# Main_board_rev2.net
KiCad netlist of a schematic drawn in EAGLE
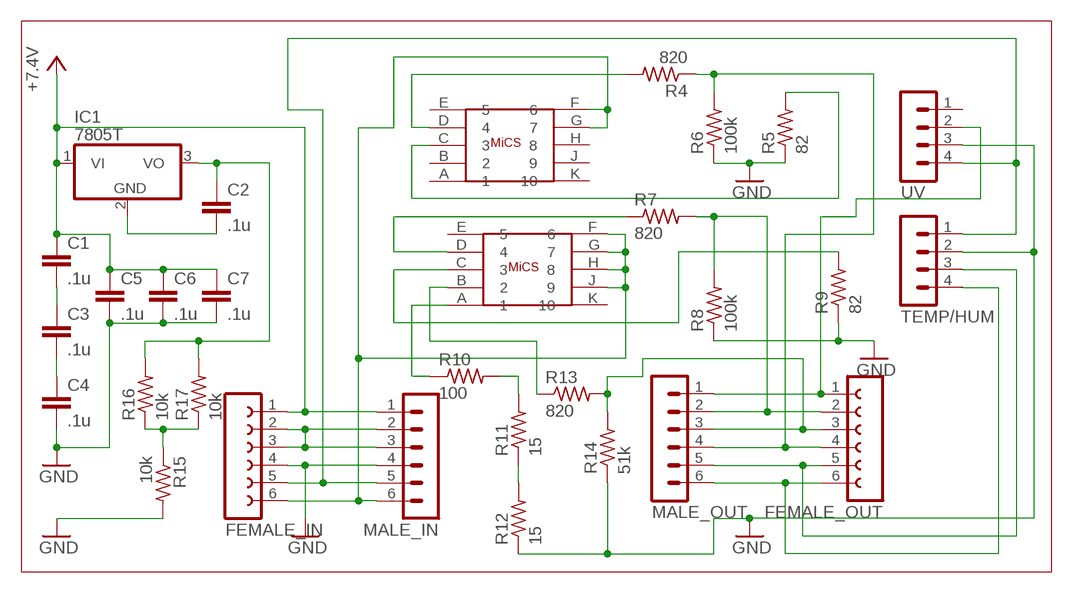
[diagram p0: schematic, sheet 1]

(export (version "E")
  (design (tool "Eeschema 10.0.6"))
  (components
    (comp (ref "2614")
      (value "MICS_SMD")
      (footprint "eagle-import:MICS_SOCKET")
      (libsource (lib "eagle-import") (part "MICS_SMD"))
    )
    (comp (ref "4514")
      (value "MICS_SMD")
      (footprint "eagle-import:MICS_SOCKET")
      (libsource (lib "eagle-import") (part "MICS_SMD"))
    )
    (comp (ref "C1")
      (value ".1u")
      (footprint "eagle-import:C2.5-3")
      (libsource (lib "eagle-import") (part "C2,5-3"))
    )
    (comp (ref "C2")
      (value ".1u")
      (footprint "eagle-import:C2.5-3")
      (libsource (lib "eagle-import") (part "C2,5-3"))
    )
    (comp (ref "C3")
      (value ".1u")
      (footprint "eagle-import:C2.5-3")
      (libsource (lib "eagle-import") (part "C2,5-3"))
    )
    (comp (ref "C4")
      (value ".1u")
      (footprint "eagle-import:C2.5-3")
      (libsource (lib "eagle-import") (part "C2,5-3"))
    )
    (comp (ref "C5")
      (value ".1u")
      (footprint "eagle-import:C2.5-3")
      (libsource (lib "eagle-import") (part "C2,5-3"))
    )
    (comp (ref "C6")
      (value ".1u")
      (footprint "eagle-import:C2.5-3")
      (libsource (lib "eagle-import") (part "C2,5-3"))
    )
    (comp (ref "C7")
      (value ".1u")
      (footprint "eagle-import:C2.5-3")
      (libsource (lib "eagle-import") (part "C2,5-3"))
    )
    (comp (ref "FEMALE_IN")
      (value "FE06W")
      (footprint "eagle-import:FE06W")
      (libsource (lib "eagle-import") (part "FE06W"))
    )
    (comp (ref "FEMALE_OUT")
      (value "FE06W")
      (footprint "eagle-import:FE06W")
      (libsource (lib "eagle-import") (part "FE06W"))
    )
    (comp (ref "IC1")
      (value "7805T")
      (footprint "eagle-import:TO220H")
      (libsource (lib "eagle-import") (part "78T05"))
    )
    (comp (ref "MALE_IN")
      (value "MA06-1")
      (footprint "eagle-import:MA06-1")
      (libsource (lib "eagle-import") (part "MA06-1"))
    )
    (comp (ref "MALE_OUT")
      (value "MA06-1")
      (footprint "eagle-import:MA06-1")
      (libsource (lib "eagle-import") (part "MA06-1"))
    )
    (comp (ref "R4")
      (value "820")
      (footprint "eagle-import:0204_7")
      (libsource (lib "eagle-import") (part "R-US_0204/7"))
    )
    (comp (ref "R5")
      (value "82")
      (footprint "eagle-import:0204_7")
      (libsource (lib "eagle-import") (part "R-US_0204/7"))
    )
    (comp (ref "R6")
      (value "100k")
      (footprint "eagle-import:0204_7")
      (libsource (lib "eagle-import") (part "R-US_0204/7"))
    )
    (comp (ref "R7")
      (value "820")
      (footprint "eagle-import:0204_7")
      (libsource (lib "eagle-import") (part "R-US_0204/7"))
    )
    (comp (ref "R8")
      (value "100k")
      (footprint "eagle-import:0204_7")
      (libsource (lib "eagle-import") (part "R-US_0204/7"))
    )
    (comp (ref "R9")
      (value "82")
      (footprint "eagle-import:0204_7")
      (libsource (lib "eagle-import") (part "R-US_0204/7"))
    )
    (comp (ref "R10")
      (value "100")
      (footprint "eagle-import:0204_7")
      (libsource (lib "eagle-import") (part "R-US_0204/7"))
    )
    (comp (ref "R11")
      (value "15")
      (footprint "eagle-import:0204_7")
      (libsource (lib "eagle-import") (part "R-US_0204/7"))
    )
    (comp (ref "R12")
      (value "15")
      (footprint "eagle-import:0204_7")
      (libsource (lib "eagle-import") (part "R-US_0204/7"))
    )
    (comp (ref "R13")
      (value "820")
      (footprint "eagle-import:0204_7")
      (libsource (lib "eagle-import") (part "R-US_0204/7"))
    )
    (comp (ref "R14")
      (value "51k")
      (footprint "eagle-import:0204_7")
      (libsource (lib "eagle-import") (part "R-US_0204/7"))
    )
    (comp (ref "R15")
      (value "10k")
      (footprint "eagle-import:0204_7")
      (libsource (lib "eagle-import") (part "resistor_R-US_0204/7"))
    )
    (comp (ref "R16")
      (value "10k")
      (footprint "eagle-import:0204_7")
      (libsource (lib "eagle-import") (part "resistor_R-US_0204/7"))
    )
    (comp (ref "R17")
      (value "10k")
      (footprint "eagle-import:0204_7")
      (libsource (lib "eagle-import") (part "resistor_R-US_0204/7"))
    )
    (comp (ref "TEMP/HUM")
      (value "MA04-1")
      (footprint "eagle-import:MA04-1")
      (libsource (lib "eagle-import") (part "MA04-1"))
    )
    (comp (ref "UV")
      (value "MA04-1")
      (footprint "eagle-import:MA04-1")
      (libsource (lib "eagle-import") (part "MA04-1"))
    )
  )
  (nets
    (net (code "1") (name "+7.4V") (class "Default")
      (node (ref "C1") (pin "1") (pinfunction "1_1") (pintype "passive"))
      (node (ref "C5") (pin "1") (pinfunction "1_1") (pintype "passive"))
      (node (ref "C6") (pin "1") (pinfunction "1_1") (pintype "passive"))
      (node (ref "C7") (pin "1") (pinfunction "1_1") (pintype "passive"))
      (node (ref "FEMALE_IN") (pin "1") (pinfunction "1_1") (pintype "passive"))
      (node (ref "IC1") (pin "1") (pinfunction "VI_1") (pintype "input"))
      (node (ref "MALE_IN") (pin "1") (pinfunction "1_1") (pintype "passive"))
    )
    (net (code "2") (name "GND") (class "Default")
      (node (ref "C4") (pin "2") (pinfunction "2_2") (pintype "passive"))
      (node (ref "C5") (pin "2") (pinfunction "2_2") (pintype "passive"))
      (node (ref "C6") (pin "2") (pinfunction "2_2") (pintype "passive"))
      (node (ref "C7") (pin "2") (pinfunction "2_2") (pintype "passive"))
      (node (ref "FEMALE_IN") (pin "4") (pinfunction "4_4") (pintype "passive"))
      (node (ref "MALE_IN") (pin "4") (pinfunction "4_4") (pintype "passive"))
      (node (ref "R12") (pin "1") (pinfunction "1_1") (pintype "passive"))
      (node (ref "R14") (pin "1") (pinfunction "1_1") (pintype "passive"))
      (node (ref "R15") (pin "2") (pinfunction "2_2") (pintype "passive"))
      (node (ref "R5") (pin "1") (pinfunction "1_1") (pintype "passive"))
      (node (ref "R6") (pin "1") (pinfunction "1_1") (pintype "passive"))
      (node (ref "R8") (pin "1") (pinfunction "1_1") (pintype "passive"))
      (node (ref "R9") (pin "1") (pinfunction "1_1") (pintype "passive"))
      (node (ref "TEMP/HUM") (pin "2") (pinfunction "2_2") (pintype "passive"))
      (node (ref "UV") (pin "3") (pinfunction "3_3") (pintype "passive"))
    )
    (net (code "3") (name "Net-(2614-3)") (class "Default")
      (node (ref "2614") (pin "C") (pinfunction "3_C") (pintype "bidirectional"))
      (node (ref "R5") (pin "2") (pinfunction "2_2") (pintype "passive"))
    )
    (net (code "4") (name "Net-(2614-4)") (class "Default")
      (node (ref "2614") (pin "D") (pinfunction "4_D") (pintype "bidirectional"))
      (node (ref "R4") (pin "2") (pinfunction "2_2") (pintype "passive"))
    )
    (net (code "5") (name "Net-(2614-6)") (class "Default")
      (node (ref "2614") (pin "F") (pinfunction "6_F") (pintype "bidirectional"))
      (node (ref "2614") (pin "G") (pinfunction "7_G") (pintype "bidirectional"))
      (node (ref "4514") (pin "F") (pinfunction "6_F") (pintype "bidirectional"))
      (node (ref "4514") (pin "G") (pinfunction "7_G") (pintype "bidirectional"))
      (node (ref "4514") (pin "H") (pinfunction "8_H") (pintype "bidirectional"))
      (node (ref "4514") (pin "J") (pinfunction "9_J") (pintype "bidirectional"))
      (node (ref "FEMALE_IN") (pin "6") (pinfunction "6_6") (pintype "passive"))
      (node (ref "MALE_IN") (pin "6") (pinfunction "6_6") (pintype "passive"))
    )
    (net (code "6") (name "Net-(4514-1)") (class "Default")
      (node (ref "4514") (pin "A") (pinfunction "1_A") (pintype "bidirectional"))
      (node (ref "R10") (pin "1") (pinfunction "1_1") (pintype "passive"))
    )
    (net (code "7") (name "Net-(4514-2)") (class "Default")
      (node (ref "4514") (pin "B") (pinfunction "2_B") (pintype "bidirectional"))
      (node (ref "R13") (pin "1") (pinfunction "1_1") (pintype "passive"))
    )
    (net (code "8") (name "Net-(4514-3)") (class "Default")
      (node (ref "4514") (pin "C") (pinfunction "3_C") (pintype "bidirectional"))
      (node (ref "R9") (pin "2") (pinfunction "2_2") (pintype "passive"))
    )
    (net (code "9") (name "Net-(4514-4)") (class "Default")
      (node (ref "4514") (pin "D") (pinfunction "4_D") (pintype "bidirectional"))
      (node (ref "R7") (pin "1") (pinfunction "1_1") (pintype "passive"))
    )
    (net (code "10") (name "Net-(C1-Pad2)") (class "Default")
      (node (ref "C1") (pin "2") (pinfunction "2_2") (pintype "passive"))
      (node (ref "C3") (pin "1") (pinfunction "1_1") (pintype "passive"))
    )
    (net (code "11") (name "Net-(C3-Pad2)") (class "Default")
      (node (ref "C3") (pin "2") (pinfunction "2_2") (pintype "passive"))
      (node (ref "C4") (pin "1") (pinfunction "1_1") (pintype "passive"))
    )
    (net (code "12") (name "Net-(FEMALE_IN-Pad2)") (class "Default")
      (node (ref "FEMALE_IN") (pin "2") (pinfunction "2_2") (pintype "passive"))
      (node (ref "FEMALE_IN") (pin "3") (pinfunction "3_3") (pintype "passive"))
      (node (ref "MALE_IN") (pin "2") (pinfunction "2_2") (pintype "passive"))
      (node (ref "MALE_IN") (pin "3") (pinfunction "3_3") (pintype "passive"))
    )
    (net (code "13") (name "Net-(FEMALE_IN-Pad5)") (class "Default")
      (node (ref "FEMALE_IN") (pin "5") (pinfunction "5_5") (pintype "passive"))
      (node (ref "MALE_IN") (pin "5") (pinfunction "5_5") (pintype "passive"))
      (node (ref "TEMP/HUM") (pin "1") (pinfunction "1_1") (pintype "passive"))
      (node (ref "UV") (pin "4") (pinfunction "4_4") (pintype "passive"))
    )
    (net (code "14") (name "Net-(FEMALE_OUT-Pad1)") (class "Default")
      (node (ref "FEMALE_OUT") (pin "1") (pinfunction "1_1") (pintype "passive"))
      (node (ref "MALE_OUT") (pin "1") (pinfunction "1_1") (pintype "passive"))
      (node (ref "UV") (pin "2") (pinfunction "2_2") (pintype "passive"))
    )
    (net (code "15") (name "Net-(FEMALE_OUT-Pad2)") (class "Default")
      (node (ref "FEMALE_OUT") (pin "2") (pinfunction "2_2") (pintype "passive"))
      (node (ref "MALE_OUT") (pin "2") (pinfunction "2_2") (pintype "passive"))
      (node (ref "R7") (pin "2") (pinfunction "2_2") (pintype "passive"))
      (node (ref "R8") (pin "2") (pinfunction "2_2") (pintype "passive"))
    )
    (net (code "16") (name "Net-(FEMALE_OUT-Pad3)") (class "Default")
      (node (ref "FEMALE_OUT") (pin "3") (pinfunction "3_3") (pintype "passive"))
      (node (ref "MALE_OUT") (pin "3") (pinfunction "3_3") (pintype "passive"))
      (node (ref "R13") (pin "2") (pinfunction "2_2") (pintype "passive"))
      (node (ref "R14") (pin "2") (pinfunction "2_2") (pintype "passive"))
    )
    (net (code "17") (name "Net-(FEMALE_OUT-Pad4)") (class "Default")
      (node (ref "FEMALE_OUT") (pin "4") (pinfunction "4_4") (pintype "passive"))
      (node (ref "MALE_OUT") (pin "4") (pinfunction "4_4") (pintype "passive"))
      (node (ref "R4") (pin "1") (pinfunction "1_1") (pintype "passive"))
      (node (ref "R6") (pin "2") (pinfunction "2_2") (pintype "passive"))
    )
    (net (code "18") (name "Net-(FEMALE_OUT-Pad5)") (class "Default")
      (node (ref "FEMALE_OUT") (pin "5") (pinfunction "5_5") (pintype "passive"))
      (node (ref "MALE_OUT") (pin "5") (pinfunction "5_5") (pintype "passive"))
      (node (ref "TEMP/HUM") (pin "3") (pinfunction "3_3") (pintype "passive"))
    )
    (net (code "19") (name "Net-(FEMALE_OUT-Pad6)") (class "Default")
      (node (ref "FEMALE_OUT") (pin "6") (pinfunction "6_6") (pintype "passive"))
      (node (ref "MALE_OUT") (pin "6") (pinfunction "6_6") (pintype "passive"))
      (node (ref "TEMP/HUM") (pin "4") (pinfunction "4_4") (pintype "passive"))
    )
    (net (code "20") (name "Net-(IC1-GND)") (class "Default")
      (node (ref "C2") (pin "2") (pinfunction "2_2") (pintype "passive"))
      (node (ref "IC1") (pin "2") (pinfunction "GND_2") (pintype "passive"))
    )
    (net (code "21") (name "Net-(IC1-VO)") (class "Default")
      (node (ref "C2") (pin "1") (pinfunction "1_1") (pintype "passive"))
      (node (ref "IC1") (pin "3") (pinfunction "VO_3") (pintype "passive"))
      (node (ref "R16") (pin "2") (pinfunction "2_2") (pintype "passive"))
      (node (ref "R17") (pin "2") (pinfunction "2_2") (pintype "passive"))
    )
    (net (code "22") (name "Net-(R10-Pad2)") (class "Default")
      (node (ref "R10") (pin "2") (pinfunction "2_2") (pintype "passive"))
      (node (ref "R11") (pin "2") (pinfunction "2_2") (pintype "passive"))
    )
    (net (code "23") (name "Net-(R11-Pad1)") (class "Default")
      (node (ref "R11") (pin "1") (pinfunction "1_1") (pintype "passive"))
      (node (ref "R12") (pin "2") (pinfunction "2_2") (pintype "passive"))
    )
    (net (code "24") (name "Net-(R15-Pad1)") (class "Default")
      (node (ref "R15") (pin "1") (pinfunction "1_1") (pintype "passive"))
      (node (ref "R16") (pin "1") (pinfunction "1_1") (pintype "passive"))
      (node (ref "R17") (pin "1") (pinfunction "1_1") (pintype "passive"))
    )
    (net (code "25") (name "unconnected-(2614-1-PadA)") (class "Default")
      (node (ref "2614") (pin "A") (pinfunction "1_A") (pintype "bidirectional"))
    )
    (net (code "26") (name "unconnected-(2614-2-PadB)") (class "Default")
      (node (ref "2614") (pin "B") (pinfunction "2_B") (pintype "bidirectional"))
    )
    (net (code "27") (name "unconnected-(2614-5-PadE)") (class "Default")
      (node (ref "2614") (pin "E") (pinfunction "5_E") (pintype "bidirectional"))
    )
    (net (code "28") (name "unconnected-(2614-8-PadH)") (class "Default")
      (node (ref "2614") (pin "H") (pinfunction "8_H") (pintype "bidirectional"))
    )
    (net (code "29") (name "unconnected-(2614-9-PadJ)") (class "Default")
      (node (ref "2614") (pin "J") (pinfunction "9_J") (pintype "bidirectional"))
    )
    (net (code "30") (name "unconnected-(2614-10-PadK)") (class "Default")
      (node (ref "2614") (pin "K") (pinfunction "10_K") (pintype "bidirectional"))
    )
    (net (code "31") (name "unconnected-(4514-5-PadE)") (class "Default")
      (node (ref "4514") (pin "E") (pinfunction "5_E") (pintype "bidirectional"))
    )
    (net (code "32") (name "unconnected-(4514-10-PadK)") (class "Default")
      (node (ref "4514") (pin "K") (pinfunction "10_K") (pintype "bidirectional"))
    )
    (net (code "33") (name "unconnected-(UV-Pad1)") (class "Default")
      (node (ref "UV") (pin "1") (pinfunction "1_1") (pintype "passive"))
    )
  )
)
